# PGA.net
KiCad netlist of a schematic drawn in Altium Designer
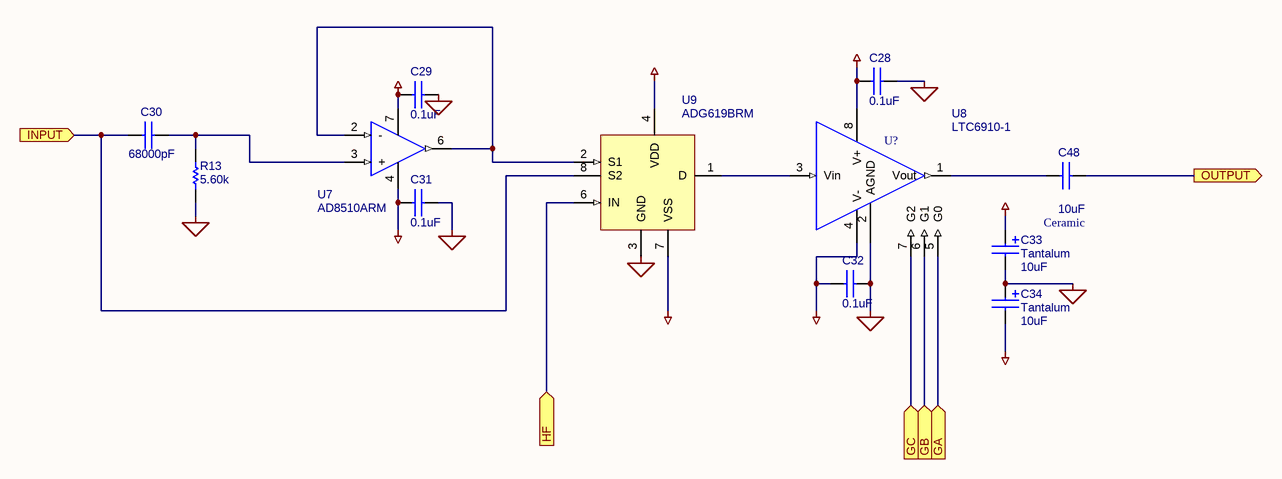
[diagram p0: PGA.SCHDOC]

(export (version "E")
  (design (tool "Eeschema 10.0.6"))
  (components
    (comp (ref "C28")
      (value "0.1uF")
      (footprint "0603")
      (description "Standard Capacitor")
      (fields (field (name "Comment") "CAPACITOR"))
      (libsource (lib "parts") (part "CAPACITOR"))
    )
    (comp (ref "C29")
      (value "0.1uF")
      (footprint "0603")
      (description "Standard Capacitor")
      (fields (field (name "Comment") "CAPACITOR"))
      (libsource (lib "parts") (part "CAPACITOR"))
    )
    (comp (ref "C30")
      (value "68000pF")
      (footprint "1206")
      (description "Standard Capacitor")
      (fields (field (name "Comment") "CAPACITOR"))
      (libsource (lib "parts") (part "CAPACITOR"))
    )
    (comp (ref "C31")
      (value "0.1uF")
      (footprint "0603")
      (description "Standard Capacitor")
      (fields (field (name "Comment") "CAPACITOR"))
      (libsource (lib "parts") (part "CAPACITOR"))
    )
    (comp (ref "C32")
      (value "0.1uF")
      (footprint "0603")
      (description "Standard Capacitor")
      (fields (field (name "Comment") "CAPACITOR"))
      (libsource (lib "parts") (part "CAPACITOR"))
    )
    (comp (ref "C33")
      (value "Tantalum")
      (footprint "3216")
      (description "Standard Capacitor")
      (fields (field (name "ALTIUM_VALUE") "10uF"))
      (libsource (lib "parts") (part "POLCAP"))
    )
    (comp (ref "C34")
      (value "Tantalum")
      (footprint "3216")
      (description "Standard Capacitor")
      (fields (field (name "ALTIUM_VALUE") "10uF"))
      (libsource (lib "parts") (part "POLCAP"))
    )
    (comp (ref "C48")
      (value "10uF")
      (footprint "0805")
      (description "Standard Capacitor")
      (fields (field (name "TYPE") "Ceramic"))
      (libsource (lib "parts") (part "CAPACITOR"))
    )
    (comp (ref "R13")
      (value "5.60k")
      (footprint "0603")
      (description "Standard Passive Resistor")
      (fields (field (name "Comment") "RESISTOR"))
      (libsource (lib "parts") (part "RESISTOR"))
    )
    (comp (ref "U7")
      (value "AD8510ARM")
      (footprint "TSSO3X5-G8/X.4")
      (description "Precision Low Noise, Low Input Bias Current Operational Amplifier")
      (libsource (lib "parts") (part "OP1177"))
    )
    (comp (ref "U8")
      (value "LTC6910-1")
      (footprint "TSOT-23-8")
      (description "LTI Digitally Controlled Programmabe Gain Amp")
      (libsource (lib "parts") (part "LTC6910-1"))
    )
    (comp (ref "U9")
      (value "ADG619BRM")
      (footprint "MSOP8")
      (description "Low RON SPDT Switch (s2 normally on)")
      (libsource (lib "parts") (part "ADG619"))
    )
  )
  (nets
    (net (code "1") (name "/GA") (class "Default")
      (node (ref "U8") (pin "5") (pinfunction "G0_5") (pintype "input"))
    )
    (net (code "2") (name "/GB") (class "Default")
      (node (ref "U8") (pin "6") (pinfunction "G1_6") (pintype "input"))
    )
    (net (code "3") (name "/GC") (class "Default")
      (node (ref "U8") (pin "7") (pinfunction "G2_7") (pintype "input"))
    )
    (net (code "4") (name "/HF") (class "Default")
      (node (ref "U9") (pin "6") (pinfunction "IN_6") (pintype "input"))
    )
    (net (code "5") (name "/INPUT") (class "Default")
      (node (ref "C30") (pin "2") (pintype "passive"))
      (node (ref "U9") (pin "8") (pinfunction "S2_8") (pintype "passive"))
    )
    (net (code "6") (name "/OUTPUT") (class "Default") (node (ref "C48") (pin "1") (pintype "passive")))
    (net (code "7") (name "AGND") (class "Default")
      (node (ref "C28") (pin "2") (pintype "passive"))
      (node (ref "C29") (pin "2") (pintype "passive"))
      (node (ref "C31") (pin "2") (pintype "passive"))
      (node (ref "C32") (pin "1") (pintype "passive"))
      (node (ref "C33") (pin "2") (pintype "passive"))
      (node (ref "C34") (pin "1") (pintype "passive"))
      (node (ref "R13") (pin "1") (pintype "passive"))
      (node (ref "U8") (pin "2") (pinfunction "AGND_2") (pintype "power_in"))
      (node (ref "U9") (pin "3") (pinfunction "GND_3") (pintype "power_in"))
    )
    (net (code "8") (name "AVDD") (class "Default")
      (node (ref "C28") (pin "1") (pintype "passive"))
      (node (ref "C29") (pin "1") (pintype "passive"))
      (node (ref "C33") (pin "1") (pintype "passive"))
      (node (ref "U7") (pin "7") (pinfunction "+Vs_7") (pintype "power_in"))
      (node (ref "U8") (pin "8") (pinfunction "V+_8") (pintype "power_in"))
      (node (ref "U9") (pin "4") (pinfunction "VDD_4") (pintype "power_in"))
    )
    (net (code "9") (name "AVSS") (class "Default")
      (node (ref "C31") (pin "1") (pintype "passive"))
      (node (ref "C32") (pin "2") (pintype "passive"))
      (node (ref "C34") (pin "2") (pintype "passive"))
      (node (ref "U7") (pin "4") (pinfunction "-Vs_4") (pintype "power_in"))
      (node (ref "U8") (pin "4") (pinfunction "V-_4") (pintype "power_in"))
      (node (ref "U9") (pin "7") (pinfunction "VSS_7") (pintype "power_in"))
    )
    (net (code "10") (name "Net-(U7-+)") (class "Default")
      (node (ref "C30") (pin "1") (pintype "passive"))
      (node (ref "R13") (pin "2") (pintype "passive"))
      (node (ref "U7") (pin "3") (pinfunction "+_3") (pintype "input"))
    )
    (net (code "11") (name "Net-(U7--)") (class "Default")
      (node (ref "U7") (pin "2") (pinfunction "-_2") (pintype "input"))
      (node (ref "U7") (pin "6") (pinfunction "Out_6") (pintype "output"))
      (node (ref "U9") (pin "2") (pinfunction "S1_2") (pintype "input"))
    )
    (net (code "12") (name "Net-(U8-Vin)") (class "Default")
      (node (ref "U8") (pin "3") (pinfunction "Vin_3") (pintype "input"))
      (node (ref "U9") (pin "1") (pinfunction "D_1") (pintype "passive"))
    )
    (net (code "13") (name "Net-(U8-Vout)") (class "Default")
      (node (ref "C48") (pin "2") (pintype "passive"))
      (node (ref "U8") (pin "1") (pinfunction "Vout_1") (pintype "output"))
    )
  )
)
